# Safety_Valve.net
KiCad netlist of a schematic drawn in EAGLE
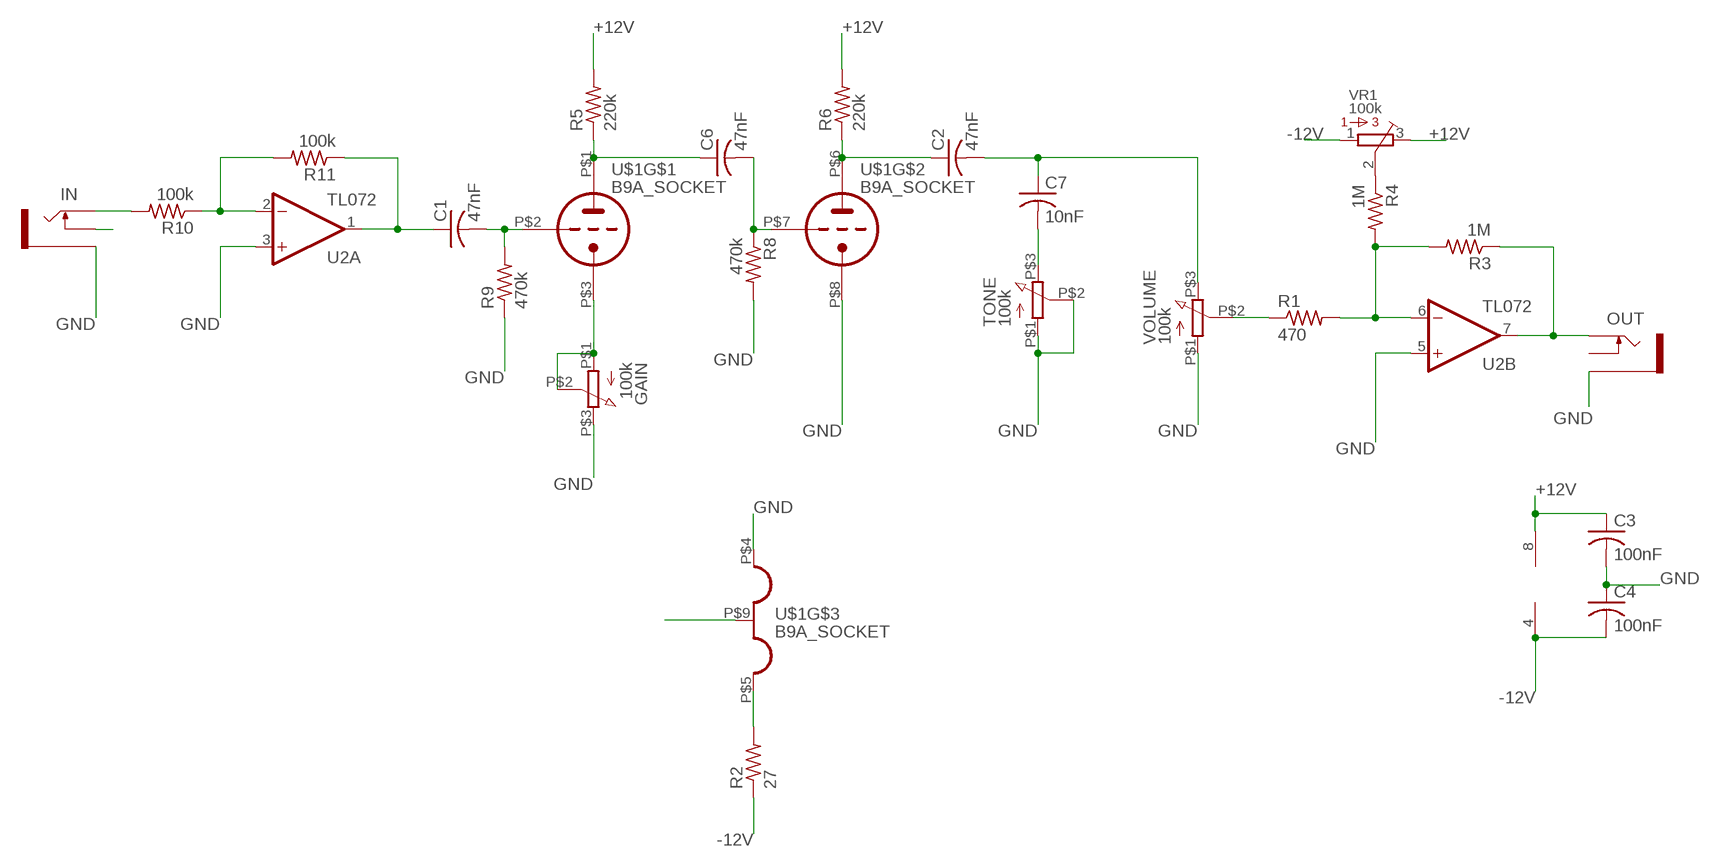
[diagram p0: schematic, sheet 1]
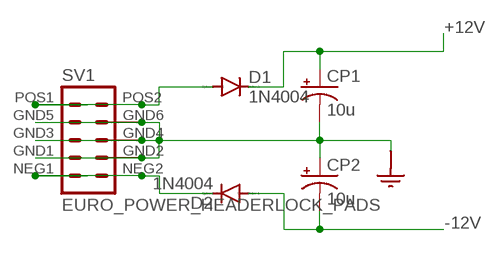
[diagram p1: schematic, sheet 2]

(export (version "E")
  (design (tool "Eeschema 10.0.6"))
  (components
    (comp (ref "CP1")
      (value "10u")
      (footprint "eagle-import:SANYO-OSCON_D")
      (fields (field (name "SPICEPREFIX") "C"))
      (libsource (lib "eagle-import") (part "CAPACITOR_POL-USSANYO_D"))
    )
    (comp (ref "CP2")
      (value "10u")
      (footprint "eagle-import:SANYO-OSCON_D")
      (fields (field (name "SPICEPREFIX") "C"))
      (libsource (lib "eagle-import") (part "CAPACITOR_POL-USSANYO_D"))
    )
    (comp (ref "D1")
      (value "1N4004")
      (footprint "eagle-import:DO41-10")
      (libsource (lib "eagle-import") (part "1N4004"))
    )
    (comp (ref "D2")
      (value "1N4004")
      (footprint "eagle-import:DO41-10")
      (libsource (lib "eagle-import") (part "1N4004"))
    )
    (comp (ref "SV1")
      (value "EURO_POWER_HEADERLOCK_PADS")
      (footprint "eagle-import:EURO_PWR_HEADER_LOCK")
      (libsource (lib "eagle-import") (part "EURO_POWER_HEADERLOCK_PADS"))
    )
    (comp (ref "C1")
      (value "47nF")
      (footprint "eagle-import:C025-024X044")
      (fields (field (name "SPICEPREFIX") "C"))
      (libsource (lib "eagle-import") (part "CAPACITOR-US025-024X044"))
    )
    (comp (ref "C2")
      (value "47nF")
      (footprint "eagle-import:C025-024X044")
      (fields (field (name "SPICEPREFIX") "C"))
      (libsource (lib "eagle-import") (part "CAPACITOR-US025-024X044"))
    )
    (comp (ref "C3")
      (value "100nF")
      (footprint "eagle-import:C025-024X044")
      (fields (field (name "SPICEPREFIX") "C"))
      (libsource (lib "eagle-import") (part "CAPACITOR-US025-024X044"))
    )
    (comp (ref "C4")
      (value "100nF")
      (footprint "eagle-import:C025-024X044")
      (fields (field (name "SPICEPREFIX") "C"))
      (libsource (lib "eagle-import") (part "CAPACITOR-US025-024X044"))
    )
    (comp (ref "C6")
      (value "47nF")
      (footprint "eagle-import:C025-024X044")
      (fields (field (name "SPICEPREFIX") "C"))
      (libsource (lib "eagle-import") (part "CAPACITOR-US025-024X044"))
    )
    (comp (ref "C7")
      (value "10nF")
      (footprint "eagle-import:C050-024X044")
      (fields (field (name "SPICEPREFIX") "C"))
      (libsource (lib "eagle-import") (part "CAPACITOR-US050-024X044"))
    )
    (comp (ref "GAIN")
      (value "100k")
      (footprint "eagle-import:POTENTIOMETER_9MM")
      (fields (field (name "SPICEPREFIX") "X"))
      (libsource (lib "eagle-import") (part "RESISTOR_VARIABLE9MM_POT"))
    )
    (comp (ref "IN")
      (value "SOCKET_MONO_3.5MMPJ301M-12")
      (footprint "eagle-import:PJ301M-12")
      (fields (field (name "SPICEMODEL") "SocketMonoSigIn") (field (name "SPICEPREFIX") "X"))
      (libsource (lib "eagle-import") (part "SOCKET_MONO_3.5MMPJ301M-12"))
    )
    (comp (ref "OUT")
      (value "SOCKET_MONO_3.5MMPJ301M-12")
      (footprint "eagle-import:PJ301M-12")
      (fields (field (name "SPICEMODEL") "SocketMono") (field (name "SPICEPREFIX") "X"))
      (libsource (lib "eagle-import") (part "SOCKET_MONO_3.5MMPJ301M-12"))
    )
    (comp (ref "R1")
      (value "470")
      (footprint "eagle-import:0207_10")
      (fields (field (name "SPICEPREFIX") "R"))
      (libsource (lib "eagle-import") (part "RESISTOR_US0207/10"))
    )
    (comp (ref "R2")
      (value "27")
      (footprint "eagle-import:0207_15")
      (libsource (lib "eagle-import") (part "R-US_0207/15"))
    )
    (comp (ref "R3")
      (value "1M")
      (footprint "eagle-import:0207_10")
      (fields (field (name "SPICEPREFIX") "R"))
      (libsource (lib "eagle-import") (part "RESISTOR_US0207/10"))
    )
    (comp (ref "R4")
      (value "1M")
      (footprint "eagle-import:0207_10")
      (fields (field (name "SPICEPREFIX") "R"))
      (libsource (lib "eagle-import") (part "RESISTOR_US0207/10"))
    )
    (comp (ref "R5")
      (value "220k")
      (footprint "eagle-import:0207_10")
      (fields (field (name "SPICEPREFIX") "R"))
      (libsource (lib "eagle-import") (part "RESISTOR_US0207/10"))
    )
    (comp (ref "R6")
      (value "220k")
      (footprint "eagle-import:0207_10")
      (fields (field (name "SPICEPREFIX") "R"))
      (libsource (lib "eagle-import") (part "RESISTOR_US0207/10"))
    )
    (comp (ref "R8")
      (value "470k")
      (footprint "eagle-import:0207_10")
      (fields (field (name "SPICEPREFIX") "R"))
      (libsource (lib "eagle-import") (part "RESISTOR_US0207/10"))
    )
    (comp (ref "R9")
      (value "470k")
      (footprint "eagle-import:0207_10")
      (fields (field (name "SPICEPREFIX") "R"))
      (libsource (lib "eagle-import") (part "RESISTOR_US0207/10"))
    )
    (comp (ref "R10")
      (value "100k")
      (footprint "eagle-import:0207_10")
      (fields (field (name "SPICEPREFIX") "R"))
      (libsource (lib "eagle-import") (part "RESISTOR_US0207/10"))
    )
    (comp (ref "R11")
      (value "100k")
      (footprint "eagle-import:0207_10")
      (fields (field (name "SPICEPREFIX") "R"))
      (libsource (lib "eagle-import") (part "RESISTOR_US0207/10"))
    )
    (comp (ref "TONE")
      (value "100k")
      (footprint "eagle-import:POTENTIOMETER_9MM")
      (fields (field (name "SPICEPREFIX") "X"))
      (libsource (lib "eagle-import") (part "RESISTOR_VARIABLE9MM_POT"))
    )
    (comp (ref "U$1")
      (value "B9A_SOCKET")
      (footprint "eagle-import:B9A_SOCKET")
      (libsource (lib "eagle-import") (part "B9A_SOCKET"))
    )
    (comp (ref "U2")
      (value "TL072")
      (footprint "eagle-import:DIL08-SML")
      (libsource (lib "eagle-import") (part "TL072"))
    )
    (comp (ref "VOLUME")
      (value "100k")
      (footprint "eagle-import:POTENTIOMETER_9MM")
      (fields (field (name "SPICEPREFIX") "X"))
      (libsource (lib "eagle-import") (part "RESISTOR_VARIABLE9MM_POT"))
    )
    (comp (ref "VR1")
      (value "100k")
      (footprint "eagle-import:BOURNS_3362P_TRIMMER")
      (libsource (lib "eagle-import") (part "BOURNS_3362P_TRIMMERP"))
    )
  )
  (nets
    (net (code "1") (name "+12V") (class "Default")
      (node (ref "C3") (pin "1") (pinfunction "1_1") (pintype "passive"))
      (node (ref "CP1") (pin "+") (pinfunction "+_+") (pintype "passive"))
      (node (ref "D1") (pin "C") (pinfunction "C_C") (pintype "passive"))
      (node (ref "R5") (pin "2") (pinfunction "2_2") (pintype "passive"))
      (node (ref "R6") (pin "2") (pinfunction "2_2") (pintype "passive"))
      (node (ref "U2") (pin "8") (pinfunction "V+_8") (pintype "power_in"))
      (node (ref "VR1") (pin "3") (pinfunction "3_3") (pintype "passive"))
    )
    (net (code "2") (name "-12V") (class "Default")
      (node (ref "C4") (pin "2") (pinfunction "2_2") (pintype "passive"))
      (node (ref "CP2") (pin "-") (pinfunction "-_-") (pintype "passive"))
      (node (ref "D2") (pin "A") (pinfunction "A_A") (pintype "passive"))
      (node (ref "R2") (pin "1") (pinfunction "1_1") (pintype "passive"))
      (node (ref "U2") (pin "4") (pinfunction "V-_4") (pintype "power_in"))
      (node (ref "VR1") (pin "1") (pinfunction "1_1") (pintype "passive"))
    )
    (net (code "3") (name "GND") (class "Default")
      (node (ref "C3") (pin "2") (pinfunction "2_2") (pintype "passive"))
      (node (ref "C4") (pin "1") (pinfunction "1_1") (pintype "passive"))
      (node (ref "CP1") (pin "-") (pinfunction "-_-") (pintype "passive"))
      (node (ref "CP2") (pin "+") (pinfunction "+_+") (pintype "passive"))
      (node (ref "GAIN") (pin "P$3") (pinfunction "3_P$3") (pintype "passive"))
      (node (ref "IN") (pin "GND") (pinfunction "SLEEVE_GND") (pintype "passive"))
      (node (ref "OUT") (pin "GND") (pinfunction "SLEEVE_GND") (pintype "passive"))
      (node (ref "R8") (pin "2") (pinfunction "2_2") (pintype "passive"))
      (node (ref "R9") (pin "1") (pinfunction "1_1") (pintype "passive"))
      (node (ref "SV1") (pin "GND1") (pinfunction "4_GND1") (pintype "passive"))
      (node (ref "SV1") (pin "GND2") (pinfunction "3_GND2") (pintype "passive"))
      (node (ref "SV1") (pin "GND3") (pinfunction "6_GND3") (pintype "passive"))
      (node (ref "SV1") (pin "GND4") (pinfunction "5_GND4") (pintype "passive"))
      (node (ref "SV1") (pin "GND5") (pinfunction "8_GND5") (pintype "passive"))
      (node (ref "SV1") (pin "GND6") (pinfunction "7_GND6") (pintype "passive"))
      (node (ref "TONE") (pin "P$1") (pinfunction "1_P$1") (pintype "passive"))
      (node (ref "TONE") (pin "P$2") (pinfunction "2_P$2") (pintype "passive"))
      (node (ref "U$1") (pin "P$4") (pinfunction "H1_P$4") (pintype "passive"))
      (node (ref "U$1") (pin "P$8") (pinfunction "TK_P$8") (pintype "passive"))
      (node (ref "U2") (pin "3") (pinfunction "+IN_3") (pintype "input"))
      (node (ref "U2") (pin "5") (pinfunction "+IN_5") (pintype "input"))
      (node (ref "VOLUME") (pin "P$1") (pinfunction "1_P$1") (pintype "passive"))
    )
    (net (code "4") (name "Net-(GAIN-1)") (class "Default")
      (node (ref "GAIN") (pin "P$1") (pinfunction "1_P$1") (pintype "passive"))
      (node (ref "GAIN") (pin "P$2") (pinfunction "2_P$2") (pintype "passive"))
      (node (ref "U$1") (pin "P$3") (pinfunction "TK_P$3") (pintype "passive"))
    )
    (net (code "5") (name "Net-(IN-PadTIP)") (class "Default")
      (node (ref "IN") (pin "TIP") (pinfunction "TIP_TIP") (pintype "passive"))
      (node (ref "R10") (pin "2") (pinfunction "2_2") (pintype "passive"))
    )
    (net (code "6") (name "Net-(R4-Pad1)") (class "Default")
      (node (ref "R4") (pin "1") (pinfunction "1_1") (pintype "passive"))
      (node (ref "VR1") (pin "2") (pinfunction "2_2") (pintype "passive"))
    )
    (net (code "7") (name "Net-(SV1-1)") (class "Default")
      (node (ref "D2") (pin "C") (pinfunction "C_C") (pintype "passive"))
      (node (ref "SV1") (pin "NEG1") (pinfunction "2_NEG1") (pintype "passive"))
      (node (ref "SV1") (pin "NEG2") (pinfunction "1_NEG2") (pintype "passive"))
    )
    (net (code "8") (name "Net-(SV1-10)") (class "Default")
      (node (ref "D1") (pin "A") (pinfunction "A_A") (pintype "passive"))
      (node (ref "SV1") (pin "POS1") (pinfunction "10_POS1") (pintype "passive"))
      (node (ref "SV1") (pin "POS2") (pinfunction "9_POS2") (pintype "passive"))
    )
    (net (code "9") (name "Net-(TONE-3)") (class "Default")
      (node (ref "C7") (pin "2") (pinfunction "2_2") (pintype "passive"))
      (node (ref "TONE") (pin "P$3") (pinfunction "3_P$3") (pintype "passive"))
    )
    (net (code "10") (name "Net-(U$1A-TA)") (class "Default")
      (node (ref "C6") (pin "1") (pinfunction "1_1") (pintype "passive"))
      (node (ref "R5") (pin "1") (pinfunction "1_1") (pintype "passive"))
      (node (ref "U$1") (pin "P$1") (pinfunction "TA_P$1") (pintype "passive"))
    )
    (net (code "11") (name "Net-(U$1A-TG)") (class "Default")
      (node (ref "C1") (pin "2") (pinfunction "2_2") (pintype "passive"))
      (node (ref "R9") (pin "2") (pinfunction "2_2") (pintype "passive"))
      (node (ref "U$1") (pin "P$2") (pinfunction "TG_P$2") (pintype "passive"))
    )
    (net (code "12") (name "Net-(U$1B-TA)") (class "Default")
      (node (ref "C2") (pin "1") (pinfunction "1_1") (pintype "passive"))
      (node (ref "R6") (pin "1") (pinfunction "1_1") (pintype "passive"))
      (node (ref "U$1") (pin "P$6") (pinfunction "TA_P$6") (pintype "passive"))
    )
    (net (code "13") (name "Net-(U$1B-TG)") (class "Default")
      (node (ref "C6") (pin "2") (pinfunction "2_2") (pintype "passive"))
      (node (ref "R8") (pin "1") (pinfunction "1_1") (pintype "passive"))
      (node (ref "U$1") (pin "P$7") (pinfunction "TG_P$7") (pintype "passive"))
    )
    (net (code "14") (name "Net-(U$1C-H3)") (class "Default")
      (node (ref "R2") (pin "2") (pinfunction "2_2") (pintype "passive"))
      (node (ref "U$1") (pin "P$5") (pinfunction "H3_P$5") (pintype "passive"))
    )
    (net (code "15") (name "Net-(U2A--IN)") (class "Default")
      (node (ref "R10") (pin "1") (pinfunction "1_1") (pintype "passive"))
      (node (ref "R11") (pin "2") (pinfunction "2_2") (pintype "passive"))
      (node (ref "U2") (pin "2") (pinfunction "-IN_2") (pintype "input"))
    )
    (net (code "16") (name "Net-(U2A-OUT)") (class "Default")
      (node (ref "C1") (pin "1") (pinfunction "1_1") (pintype "passive"))
      (node (ref "R11") (pin "1") (pinfunction "1_1") (pintype "passive"))
      (node (ref "U2") (pin "1") (pinfunction "OUT_1") (pintype "output"))
    )
    (net (code "17") (name "Net-(U2B--IN)") (class "Default")
      (node (ref "R1") (pin "2") (pinfunction "2_2") (pintype "passive"))
      (node (ref "R3") (pin "2") (pinfunction "2_2") (pintype "passive"))
      (node (ref "R4") (pin "2") (pinfunction "2_2") (pintype "passive"))
      (node (ref "U2") (pin "6") (pinfunction "-IN_6") (pintype "input"))
    )
    (net (code "18") (name "Net-(U2B-OUT)") (class "Default")
      (node (ref "OUT") (pin "TIP") (pinfunction "TIP_TIP") (pintype "passive"))
      (node (ref "R3") (pin "1") (pinfunction "1_1") (pintype "passive"))
      (node (ref "U2") (pin "7") (pinfunction "OUT_7") (pintype "output"))
    )
    (net (code "19") (name "Net-(VOLUME-2)") (class "Default")
      (node (ref "R1") (pin "1") (pinfunction "1_1") (pintype "passive"))
      (node (ref "VOLUME") (pin "P$2") (pinfunction "2_P$2") (pintype "passive"))
    )
    (net (code "20") (name "Net-(VOLUME-3)") (class "Default")
      (node (ref "C2") (pin "2") (pinfunction "2_2") (pintype "passive"))
      (node (ref "C7") (pin "1") (pinfunction "1_1") (pintype "passive"))
      (node (ref "VOLUME") (pin "P$3") (pinfunction "3_P$3") (pintype "passive"))
    )
    (net (code "21") (name "unconnected-(IN-SWITCH-PadNORM)") (class "Default")
      (node (ref "IN") (pin "NORM") (pinfunction "SWITCH_NORM") (pintype "passive"))
    )
    (net (code "22") (name "unconnected-(OUT-SWITCH-PadNORM)") (class "Default")
      (node (ref "OUT") (pin "NORM") (pinfunction "SWITCH_NORM") (pintype "passive"))
    )
    (net (code "23") (name "unconnected-(U$1C-H2-PadP$9)") (class "Default")
      (node (ref "U$1") (pin "P$9") (pinfunction "H2_P$9") (pintype "passive"))
    )
  )
)
